# 09_-_M_2-SDMMC2.net
KiCad netlist of a schematic drawn in Altium Designer
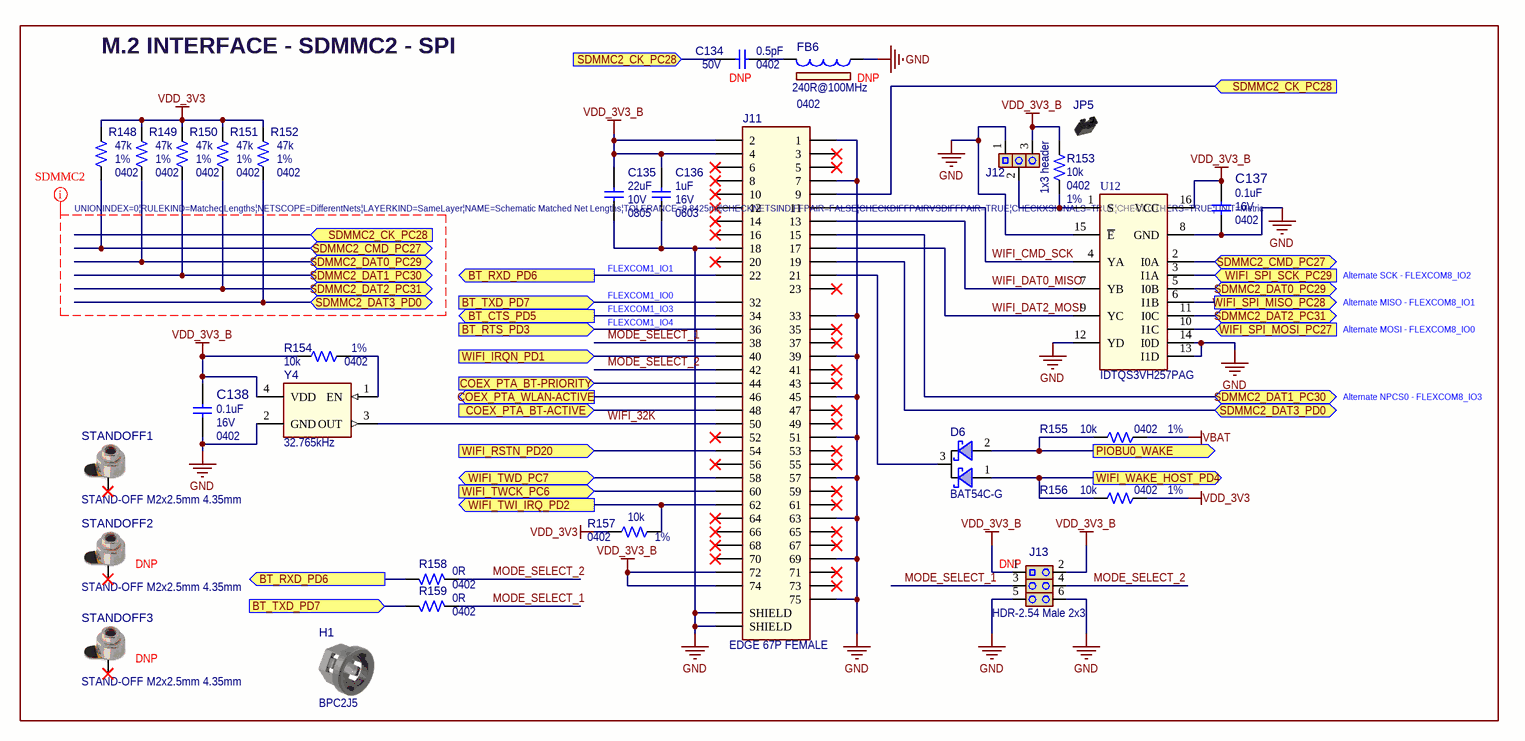
[diagram p0: 09 - M.2-SDMMC2.SchDoc]

(export (version "E")
  (design (tool "Eeschema 10.0.6"))
  (components
    (comp (ref "C134")
      (value "0.5pF")
      (footprint "CAP_C_0402")
      (fields
        (field (name "VOLTAGE") "50V")
        (field (name "PACKAGE") "0402")
        (field (name "TOLERANCE") "0.25pF")
        (field (name "POPULATED") "DNP")
        (field (name "Comment") "Capacitor NP")
      )
      (libsource (lib "MCHP-CDB") (part "Capacitor NP"))
    )
    (comp (ref "C135")
      (value "22uF")
      (footprint "CAP_C_0805")
      (fields
        (field (name "VOLTAGE") "10V")
        (field (name "PACKAGE") "0805")
        (field (name "TOLERANCE") "20%")
        (field (name "Comment") "Capacitor NP")
        (field (name "OWNER") "Razvan Cristescu")
      )
      (libsource (lib "MCHP-CDB") (part "Capacitor NP"))
    )
    (comp (ref "C136")
      (value "1uF")
      (footprint "CAP_C_0603")
      (fields
        (field (name "VOLTAGE") "16V")
        (field (name "PACKAGE") "0603")
        (field (name "TOLERANCE") "10%")
        (field (name "Comment") "Capacitor NP")
      )
      (libsource (lib "MCHP-CDB") (part "Capacitor NP"))
    )
    (comp (ref "C137")
      (value "0.1uF")
      (footprint "CAP_C_0402")
      (fields
        (field (name "VOLTAGE") "16V")
        (field (name "PACKAGE") "0402")
        (field (name "TOLERANCE") "10%")
        (field (name "Comment") "Capacitor NP")
        (field (name "OWNER") "Sompoch Loboonlert")
      )
      (libsource (lib "MCHP-CDB") (part "Capacitor NP"))
    )
    (comp (ref "C138")
      (value "0.1uF")
      (footprint "CAP_C_0402")
      (fields
        (field (name "VOLTAGE") "16V")
        (field (name "PACKAGE") "0402")
        (field (name "TOLERANCE") "10%")
        (field (name "Comment") "Capacitor NP")
        (field (name "OWNER") "Sompoch Loboonlert")
      )
      (libsource (lib "MCHP-CDB") (part "Capacitor NP"))
    )
    (comp (ref "D6")
      (value "BAT54C-G")
      (footprint "SOT-23-3")
      (fields
        (field (name "POWER") "225mW")
        (field (name "Comment") "Diode Schottky Dual CK")
        (field (name "OWNER") "Cristina Salanti")
      )
      (libsource (lib "MCHP-CDB") (part "Diode Schottky Dual CK"))
    )
    (comp (ref "FB6")
      (value "240R@100MHz")
      (footprint "IND_C_0402")
      (fields
        (field (name "PACKAGE") "0402")
        (field (name "POPULATED") "DNP")
        (field (name "Comment") "Ferrite Bead")
        (field (name "OWNER") "Joerg Buehrer")
      )
      (libsource (lib "MCHP-CDB") (part "Ferrite Bead"))
    )
    (comp (ref "H1")
      (value "BPC2J5")
      (footprint "BPC2J5")
      (fields (field (name "OWNER") "Dragos Danaila"))
      (libsource (lib "MCHP-CDB") (part "BPC2J5"))
    )
    (comp (ref "J11")
      (value "EDGE 67P FEMALE")
      (footprint "CON_EDGE-CARD_SMD_RA_TE_2199230-4")
      (fields
        (field (name "Comment") "CONN EDGE DUAL FEMALE_2199230-4")
        (field (name "OWNER") "Pilar Alcaine")
      )
      (libsource (lib "MCHP-CDB") (part "CONN EDGE DUAL FEMALE_2199230-4"))
    )
    (comp (ref "J12")
      (value "1x3 header")
      (footprint "HDR_M_2.54_1x3")
      (fields (field (name "Comment") "Header 1x3") (field (name "OWNER") "Dragos Danaila"))
      (libsource (lib "MCHP-CDB") (part "Header 1x3"))
    )
    (comp (ref "J13")
      (value "HDR-2.54 Male 2x3")
      (footprint "HDR_M_2.54_2x3")
      (fields (field (name "POPULATED") "DNP") (field (name "Comment") "Header 2x3"))
      (libsource (lib "MCHP-CDB") (part "Header 2x3"))
    )
    (comp (ref "JP5")
      (value "Jumper Mechanical")
      (footprint "Jumper_Mechanical")
      (fields (field (name "OWNER") "Narasimha Murthy"))
      (libsource (lib "MCHP-CDB") (part "Jumper Mechanical"))
    )
    (comp (ref "R148")
      (value "47k")
      (footprint "RES_C_0402")
      (description "Resistor")
      (fields
        (field (name "PACKAGE") "0402")
        (field (name "TOLERANCE") "1%")
        (field (name "VOLTAGE") "50V")
        (field (name "POWER") "1/10W")
        (field (name "OWNER") "Mike Ragsdale")
      )
      (libsource (lib "MCHP-CDB") (part "Resistor"))
    )
    (comp (ref "R149")
      (value "47k")
      (footprint "RES_C_0402")
      (description "Resistor")
      (fields
        (field (name "PACKAGE") "0402")
        (field (name "TOLERANCE") "1%")
        (field (name "VOLTAGE") "50V")
        (field (name "POWER") "1/10W")
        (field (name "OWNER") "Mike Ragsdale")
      )
      (libsource (lib "MCHP-CDB") (part "Resistor"))
    )
    (comp (ref "R150")
      (value "47k")
      (footprint "RES_C_0402")
      (description "Resistor")
      (fields
        (field (name "PACKAGE") "0402")
        (field (name "TOLERANCE") "1%")
        (field (name "VOLTAGE") "50V")
        (field (name "POWER") "1/10W")
        (field (name "OWNER") "Mike Ragsdale")
      )
      (libsource (lib "MCHP-CDB") (part "Resistor"))
    )
    (comp (ref "R151")
      (value "47k")
      (footprint "RES_C_0402")
      (description "Resistor")
      (fields
        (field (name "PACKAGE") "0402")
        (field (name "TOLERANCE") "1%")
        (field (name "VOLTAGE") "50V")
        (field (name "POWER") "1/10W")
        (field (name "OWNER") "Mike Ragsdale")
      )
      (libsource (lib "MCHP-CDB") (part "Resistor"))
    )
    (comp (ref "R152")
      (value "47k")
      (footprint "RES_C_0402")
      (description "Resistor")
      (fields
        (field (name "PACKAGE") "0402")
        (field (name "TOLERANCE") "1%")
        (field (name "VOLTAGE") "50V")
        (field (name "POWER") "1/10W")
        (field (name "OWNER") "Mike Ragsdale")
      )
      (libsource (lib "MCHP-CDB") (part "Resistor"))
    )
    (comp (ref "R153")
      (value "10k")
      (footprint "RES_C_0402")
      (description "Resistor")
      (fields
        (field (name "PACKAGE") "0402")
        (field (name "TOLERANCE") "1%")
        (field (name "VOLTAGE") "50V")
        (field (name "POWER") "1/10W")
        (field (name "OWNER") "Brent Lanphear")
      )
      (libsource (lib "MCHP-CDB") (part "Resistor"))
    )
    (comp (ref "R154")
      (value "10k")
      (footprint "RES_C_0402")
      (description "Resistor")
      (fields
        (field (name "PACKAGE") "0402")
        (field (name "TOLERANCE") "1%")
        (field (name "VOLTAGE") "50V")
        (field (name "POWER") "1/10W")
        (field (name "OWNER") "Brent Lanphear")
      )
      (libsource (lib "MCHP-CDB") (part "Resistor"))
    )
    (comp (ref "R155")
      (value "10k")
      (footprint "RES_C_0402")
      (description "Resistor")
      (fields
        (field (name "PACKAGE") "0402")
        (field (name "TOLERANCE") "1%")
        (field (name "VOLTAGE") "50V")
        (field (name "POWER") "1/10W")
        (field (name "OWNER") "Brent Lanphear")
      )
      (libsource (lib "MCHP-CDB") (part "Resistor"))
    )
    (comp (ref "R156")
      (value "10k")
      (footprint "RES_C_0402")
      (description "Resistor")
      (fields
        (field (name "PACKAGE") "0402")
        (field (name "TOLERANCE") "1%")
        (field (name "VOLTAGE") "50V")
        (field (name "POWER") "1/10W")
        (field (name "OWNER") "Brent Lanphear")
      )
      (libsource (lib "MCHP-CDB") (part "Resistor"))
    )
    (comp (ref "R157")
      (value "10k")
      (footprint "RES_C_0402")
      (description "Resistor")
      (fields
        (field (name "PACKAGE") "0402")
        (field (name "TOLERANCE") "1%")
        (field (name "VOLTAGE") "50V")
        (field (name "POWER") "1/10W")
        (field (name "OWNER") "Brent Lanphear")
      )
      (libsource (lib "MCHP-CDB") (part "Resistor"))
    )
    (comp (ref "R158")
      (value "0R")
      (footprint "RES_C_0402")
      (description "Resistor")
      (fields
        (field (name "PACKAGE") "0402")
        (field (name "POWER") "1/16W")
        (field (name "OWNER") "Sompoch Loboonlert")
      )
      (libsource (lib "") (part "Resistor_1"))
    )
    (comp (ref "R159")
      (value "0R")
      (footprint "RES_C_0402")
      (description "Resistor")
      (fields
        (field (name "PACKAGE") "0402")
        (field (name "POWER") "1/16W")
        (field (name "OWNER") "Sompoch Loboonlert")
      )
      (libsource (lib "") (part "Resistor_1"))
    )
    (comp (ref "STANDOFF1")
      (value "STAND-OFF M2x2.5mm 4.35mm")
      (footprint "MECH_HW_STAND-OFF_9774025243")
      (fields (field (name "Comment") "Standoff M-F") (field (name "OWNER") "Pilar Alcaine"))
      (libsource (lib "MCHP-CDB") (part "MECH_HW_STAND-OFF_TH_SOLDERABLE"))
    )
    (comp (ref "STANDOFF2")
      (value "STAND-OFF M2x2.5mm 4.35mm")
      (footprint "MECH_HW_STAND-OFF_9774025243")
      (fields
        (field (name "POPULATED") "DNP")
        (field (name "Comment") "Standoff M-F")
        (field (name "OWNER") "Pilar Alcaine")
      )
      (libsource (lib "MCHP-CDB") (part "MECH_HW_STAND-OFF_TH_SOLDERABLE"))
    )
    (comp (ref "STANDOFF3")
      (value "STAND-OFF M2x2.5mm 4.35mm")
      (footprint "MECH_HW_STAND-OFF_9774025243")
      (fields
        (field (name "POPULATED") "DNP")
        (field (name "Comment") "Standoff M-F")
        (field (name "OWNER") "Pilar Alcaine")
      )
      (libsource (lib "MCHP-CDB") (part "MECH_HW_STAND-OFF_TH_SOLDERABLE"))
    )
    (comp (ref "U12")
      (value "IDTQS3VH257PAG")
      (footprint "TSSOP-16")
      (fields (field (name "Comment") "IDTQS3VH257 TSSOP-16") (field (name "OWNER") "Ilie Galan"))
      (libsource (lib "MCHP-CDB") (part "IDTQS3VH257 TSSOP-16"))
    )
    (comp (ref "Y4")
      (value "32.765kHz")
      (footprint "OSCILLATOR_ASAK_L2W1.6H0.7")
      (fields
        (field (name "VOLTAGE") "3.3V")
        (field (name "TOLERANCE") "3ppm")
        (field (name "Comment") "OSCILLATOR 4 Pins")
        (field (name "OWNER") "Ilie Galan")
      )
      (libsource (lib "MCHP-CDB") (part "OSCILLATOR 4 Pins"))
    )
  )
  (nets
    (net (code "1") (name "/BT_CTS_PD5") (class "Default")
      (node (ref "J11") (pin "34") (pinfunction "34_34") (pintype "passive"))
    )
    (net (code "2") (name "/BT_RTS_PD3") (class "Default")
      (node (ref "J11") (pin "36") (pinfunction "36_36") (pintype "passive"))
    )
    (net (code "3") (name "/BT_RXD_PD6") (class "Default")
      (node (ref "J11") (pin "22") (pinfunction "22_22") (pintype "passive"))
      (node (ref "R158") (pin "1") (pinfunction "1_1") (pintype "passive"))
    )
    (net (code "4") (name "/BT_TXD_PD7") (class "Default")
      (node (ref "J11") (pin "32") (pinfunction "32_32") (pintype "passive"))
      (node (ref "R159") (pin "1") (pinfunction "1_1") (pintype "passive"))
    )
    (net (code "5") (name "/COEX_PTA_BT-ACTIVE") (class "Default")
      (node (ref "J11") (pin "48") (pinfunction "48_48") (pintype "passive"))
    )
    (net (code "6") (name "/COEX_PTA_BT-PRIORITY") (class "Default")
      (node (ref "J11") (pin "44") (pinfunction "44_44") (pintype "passive"))
    )
    (net (code "7") (name "/COEX_PTA_WLAN-ACTIVE") (class "Default")
      (node (ref "J11") (pin "46") (pinfunction "46_46") (pintype "passive"))
    )
    (net (code "8") (name "/MODE_SELECT_1") (class "Default")
      (node (ref "J11") (pin "38") (pinfunction "38_38") (pintype "passive"))
      (node (ref "J13") (pin "3") (pinfunction "3_3") (pintype "passive"))
      (node (ref "R159") (pin "2") (pinfunction "2_2") (pintype "passive"))
    )
    (net (code "9") (name "/MODE_SELECT_2") (class "Default")
      (node (ref "J11") (pin "42") (pinfunction "42_42") (pintype "passive"))
      (node (ref "J13") (pin "4") (pinfunction "4_4") (pintype "passive"))
      (node (ref "R158") (pin "2") (pinfunction "2_2") (pintype "passive"))
    )
    (net (code "10") (name "/PIOBU0_WAKE") (class "Default")
      (node (ref "D6") (pin "2") (pinfunction "A_2") (pintype "passive"))
      (node (ref "R155") (pin "2") (pinfunction "2_2") (pintype "passive"))
    )
    (net (code "11") (name "/SDMMC2_CK_PC28") (class "Default")
      (node (ref "C134") (pin "2") (pinfunction "2_2") (pintype "passive"))
      (node (ref "J11") (pin "9") (pinfunction "9_9") (pintype "passive"))
    )
    (net (code "12") (name "/SDMMC2_CMD_PC27") (class "Default")
      (node (ref "R148") (pin "2") (pinfunction "2_2") (pintype "passive"))
      (node (ref "U12") (pin "2") (pinfunction "I0A_2") (pintype "passive"))
    )
    (net (code "13") (name "/SDMMC2_DAT0_PC29") (class "Default")
      (node (ref "R149") (pin "2") (pinfunction "2_2") (pintype "passive"))
      (node (ref "U12") (pin "5") (pinfunction "I0B_5") (pintype "passive"))
    )
    (net (code "14") (name "/SDMMC2_DAT1_PC30") (class "Default")
      (node (ref "J11") (pin "15") (pinfunction "15_15") (pintype "passive"))
      (node (ref "R150") (pin "2") (pinfunction "2_2") (pintype "passive"))
    )
    (net (code "15") (name "/SDMMC2_DAT2_PC31") (class "Default")
      (node (ref "R151") (pin "2") (pinfunction "2_2") (pintype "passive"))
      (node (ref "U12") (pin "11") (pinfunction "I0C_11") (pintype "passive"))
    )
    (net (code "16") (name "/SDMMC2_DAT3_PD0") (class "Default")
      (node (ref "J11") (pin "19") (pinfunction "19_19") (pintype "passive"))
      (node (ref "R152") (pin "2") (pinfunction "2_2") (pintype "passive"))
    )
    (net (code "17") (name "/WIFI_32K") (class "Default")
      (node (ref "J11") (pin "50") (pinfunction "50_50") (pintype "passive"))
      (node (ref "Y4") (pin "3") (pinfunction "OUT_3") (pintype "output"))
    )
    (net (code "18") (name "/WIFI_CMD_SCK") (class "Default")
      (node (ref "J11") (pin "11") (pinfunction "11_11") (pintype "passive"))
      (node (ref "U12") (pin "4") (pinfunction "YA_4") (pintype "passive"))
    )
    (net (code "19") (name "/WIFI_DAT0_MISO") (class "Default")
      (node (ref "J11") (pin "13") (pinfunction "13_13") (pintype "passive"))
      (node (ref "U12") (pin "7") (pinfunction "YB_7") (pintype "passive"))
    )
    (net (code "20") (name "/WIFI_DAT2_MOSI") (class "Default")
      (node (ref "J11") (pin "17") (pinfunction "17_17") (pintype "passive"))
      (node (ref "U12") (pin "9") (pinfunction "YC_9") (pintype "passive"))
    )
    (net (code "21") (name "/WIFI_IRQN_PD1") (class "Default")
      (node (ref "J11") (pin "40") (pinfunction "40_40") (pintype "passive"))
    )
    (net (code "22") (name "/WIFI_RSTN_PD20") (class "Default")
      (node (ref "J11") (pin "54") (pinfunction "54_54") (pintype "passive"))
    )
    (net (code "23") (name "/WIFI_SPI_MISO_PC28") (class "Default")
      (node (ref "U12") (pin "6") (pinfunction "I1B_6") (pintype "passive"))
    )
    (net (code "24") (name "/WIFI_SPI_MOSI_PC27") (class "Default")
      (node (ref "U12") (pin "10") (pinfunction "I1C_10") (pintype "passive"))
    )
    (net (code "25") (name "/WIFI_SPI_SCK_PC29") (class "Default")
      (node (ref "U12") (pin "3") (pinfunction "I1A_3") (pintype "passive"))
    )
    (net (code "26") (name "/WIFI_TWCK_PC6") (class "Default")
      (node (ref "J11") (pin "60") (pinfunction "60_60") (pintype "passive"))
    )
    (net (code "27") (name "/WIFI_TWD_PC7") (class "Default")
      (node (ref "J11") (pin "58") (pinfunction "58_58") (pintype "passive"))
    )
    (net (code "28") (name "/WIFI_TWI_IRQ_PD2") (class "Default")
      (node (ref "J11") (pin "62") (pinfunction "62_62") (pintype "passive"))
      (node (ref "R157") (pin "1") (pinfunction "1_1") (pintype "passive"))
    )
    (net (code "29") (name "/WIFI_WAKE_HOST_PD4") (class "Default")
      (node (ref "D6") (pin "1") (pinfunction "A_1") (pintype "passive"))
      (node (ref "R156") (pin "2") (pinfunction "2_2") (pintype "passive"))
    )
    (net (code "30") (name "GND") (class "Default")
      (node (ref "C135") (pin "1") (pinfunction "1_1") (pintype "passive"))
      (node (ref "C136") (pin "1") (pinfunction "1_1") (pintype "passive"))
      (node (ref "C137") (pin "2") (pinfunction "2_2") (pintype "passive"))
      (node (ref "C138") (pin "2") (pinfunction "2_2") (pintype "passive"))
      (node (ref "FB6") (pin "1") (pinfunction "1_1") (pintype "passive"))
      (node (ref "J11") (pin "1") (pinfunction "1_1") (pintype "passive"))
      (node (ref "J11") (pin "18") (pinfunction "18_18") (pintype "passive"))
      (node (ref "J11") (pin "33") (pinfunction "33_33") (pintype "passive"))
      (node (ref "J11") (pin "39") (pinfunction "39_39") (pintype "passive"))
      (node (ref "J11") (pin "45") (pinfunction "45_45") (pintype "passive"))
      (node (ref "J11") (pin "51") (pinfunction "51_51") (pintype "passive"))
      (node (ref "J11") (pin "57") (pinfunction "57_57") (pintype "passive"))
      (node (ref "J11") (pin "63") (pinfunction "63_63") (pintype "passive"))
      (node (ref "J11") (pin "69") (pinfunction "69_69") (pintype "passive"))
      (node (ref "J11") (pin "7") (pinfunction "7_7") (pintype "passive"))
      (node (ref "J11") (pin "75") (pinfunction "75_75") (pintype "passive"))
      (node (ref "J11") (pin "S1") (pinfunction "SHIELD_S1") (pintype "passive"))
      (node (ref "J11") (pin "S2") (pinfunction "SHIELD_S2") (pintype "passive"))
      (node (ref "J12") (pin "1") (pinfunction "1_1") (pintype "passive"))
      (node (ref "J13") (pin "5") (pinfunction "5_5") (pintype "passive"))
      (node (ref "J13") (pin "6") (pinfunction "6_6") (pintype "passive"))
      (node (ref "U12") (pin "12") (pinfunction "YD_12") (pintype "passive"))
      (node (ref "U12") (pin "13") (pinfunction "I1D_13") (pintype "passive"))
      (node (ref "U12") (pin "14") (pinfunction "I0D_14") (pintype "passive"))
      (node (ref "U12") (pin "15") (pinfunction "~{E}_15") (pintype "passive"))
      (node (ref "U12") (pin "8") (pinfunction "GND_8") (pintype "passive"))
      (node (ref "Y4") (pin "2") (pinfunction "GND_2") (pintype "power_in"))
    )
    (net (code "31") (name "Net-(C134-Pad1)") (class "Default")
      (node (ref "C134") (pin "1") (pinfunction "1_1") (pintype "passive"))
      (node (ref "FB6") (pin "2") (pinfunction "2_2") (pintype "passive"))
    )
    (net (code "32") (name "Net-(D6-KK)") (class "Default")
      (node (ref "D6") (pin "3") (pinfunction "KK_3") (pintype "passive"))
      (node (ref "J11") (pin "21") (pinfunction "21_21") (pintype "passive"))
    )
    (net (code "33") (name "Net-(U12-S)") (class "Default")
      (node (ref "J12") (pin "2") (pinfunction "2_2") (pintype "passive"))
      (node (ref "R153") (pin "2") (pinfunction "2_2") (pintype "passive"))
      (node (ref "U12") (pin "1") (pinfunction "S_1") (pintype "passive"))
    )
    (net (code "34") (name "Net-(Y4-EN)") (class "Default")
      (node (ref "R154") (pin "1") (pinfunction "1_1") (pintype "passive"))
      (node (ref "Y4") (pin "1") (pinfunction "EN_1") (pintype "input"))
    )
    (net (code "35") (name "VBAT") (class "Default")
      (node (ref "R155") (pin "1") (pinfunction "1_1") (pintype "passive"))
    )
    (net (code "36") (name "VDD_3V3") (class "Default")
      (node (ref "R148") (pin "1") (pinfunction "1_1") (pintype "passive"))
      (node (ref "R149") (pin "1") (pinfunction "1_1") (pintype "passive"))
      (node (ref "R150") (pin "1") (pinfunction "1_1") (pintype "passive"))
      (node (ref "R151") (pin "1") (pinfunction "1_1") (pintype "passive"))
      (node (ref "R152") (pin "1") (pinfunction "1_1") (pintype "passive"))
      (node (ref "R156") (pin "1") (pinfunction "1_1") (pintype "passive"))
      (node (ref "R157") (pin "2") (pinfunction "2_2") (pintype "passive"))
    )
    (net (code "37") (name "VDD_3V3_B") (class "Default")
      (node (ref "C135") (pin "2") (pinfunction "2_2") (pintype "passive"))
      (node (ref "C136") (pin "2") (pinfunction "2_2") (pintype "passive"))
      (node (ref "C137") (pin "1") (pinfunction "1_1") (pintype "passive"))
      (node (ref "C138") (pin "1") (pinfunction "1_1") (pintype "passive"))
      (node (ref "J11") (pin "2") (pinfunction "2_2") (pintype "passive"))
      (node (ref "J11") (pin "4") (pinfunction "4_4") (pintype "passive"))
      (node (ref "J11") (pin "72") (pinfunction "72_72") (pintype "passive"))
      (node (ref "J11") (pin "74") (pinfunction "74_74") (pintype "passive"))
      (node (ref "J12") (pin "3") (pinfunction "3_3") (pintype "passive"))
      (node (ref "J13") (pin "1") (pinfunction "1_1") (pintype "passive"))
      (node (ref "J13") (pin "2") (pinfunction "2_2") (pintype "passive"))
      (node (ref "R153") (pin "1") (pinfunction "1_1") (pintype "passive"))
      (node (ref "R154") (pin "2") (pinfunction "2_2") (pintype "passive"))
      (node (ref "U12") (pin "16") (pinfunction "VCC_16") (pintype "passive"))
      (node (ref "Y4") (pin "4") (pinfunction "VDD_4") (pintype "power_in"))
    )
    (net (code "38") (name "unconnected-(J11-Pad3)") (class "Default")
      (node (ref "J11") (pin "3") (pinfunction "3_3") (pintype "passive+no_connect"))
    )
    (net (code "39") (name "unconnected-(J11-Pad5)") (class "Default")
      (node (ref "J11") (pin "5") (pinfunction "5_5") (pintype "passive+no_connect"))
    )
    (net (code "40") (name "unconnected-(J11-Pad6)") (class "Default")
      (node (ref "J11") (pin "6") (pinfunction "6_6") (pintype "passive+no_connect"))
    )
    (net (code "41") (name "unconnected-(J11-Pad8)") (class "Default")
      (node (ref "J11") (pin "8") (pinfunction "8_8") (pintype "passive+no_connect"))
    )
    (net (code "42") (name "unconnected-(J11-Pad10)") (class "Default")
      (node (ref "J11") (pin "10") (pinfunction "10_10") (pintype "passive+no_connect"))
    )
    (net (code "43") (name "unconnected-(J11-Pad12)") (class "Default")
      (node (ref "J11") (pin "12") (pinfunction "12_12") (pintype "passive+no_connect"))
    )
    (net (code "44") (name "unconnected-(J11-Pad14)") (class "Default")
      (node (ref "J11") (pin "14") (pinfunction "14_14") (pintype "passive+no_connect"))
    )
    (net (code "45") (name "unconnected-(J11-Pad16)") (class "Default")
      (node (ref "J11") (pin "16") (pinfunction "16_16") (pintype "passive+no_connect"))
    )
    (net (code "46") (name "unconnected-(J11-Pad20)") (class "Default")
      (node (ref "J11") (pin "20") (pinfunction "20_20") (pintype "passive+no_connect"))
    )
    (net (code "47") (name "unconnected-(J11-Pad23)") (class "Default")
      (node (ref "J11") (pin "23") (pinfunction "23_23") (pintype "passive+no_connect"))
    )
    (net (code "48") (name "unconnected-(J11-Pad35)") (class "Default")
      (node (ref "J11") (pin "35") (pinfunction "35_35") (pintype "passive+no_connect"))
    )
    (net (code "49") (name "unconnected-(J11-Pad37)") (class "Default")
      (node (ref "J11") (pin "37") (pinfunction "37_37") (pintype "passive+no_connect"))
    )
    (net (code "50") (name "unconnected-(J11-Pad41)") (class "Default")
      (node (ref "J11") (pin "41") (pinfunction "41_41") (pintype "passive+no_connect"))
    )
    (net (code "51") (name "unconnected-(J11-Pad43)") (class "Default")
      (node (ref "J11") (pin "43") (pinfunction "43_43") (pintype "passive+no_connect"))
    )
    (net (code "52") (name "unconnected-(J11-Pad47)") (class "Default")
      (node (ref "J11") (pin "47") (pinfunction "47_47") (pintype "passive+no_connect"))
    )
    (net (code "53") (name "unconnected-(J11-Pad49)") (class "Default")
      (node (ref "J11") (pin "49") (pinfunction "49_49") (pintype "passive+no_connect"))
    )
    (net (code "54") (name "unconnected-(J11-Pad52)") (class "Default")
      (node (ref "J11") (pin "52") (pinfunction "52_52") (pintype "passive+no_connect"))
    )
    (net (code "55") (name "unconnected-(J11-Pad53)") (class "Default")
      (node (ref "J11") (pin "53") (pinfunction "53_53") (pintype "passive+no_connect"))
    )
    (net (code "56") (name "unconnected-(J11-Pad55)") (class "Default")
      (node (ref "J11") (pin "55") (pinfunction "55_55") (pintype "passive+no_connect"))
    )
    (net (code "57") (name "unconnected-(J11-Pad56)") (class "Default")
      (node (ref "J11") (pin "56") (pinfunction "56_56") (pintype "passive+no_connect"))
    )
    (net (code "58") (name "unconnected-(J11-Pad59)") (class "Default")
      (node (ref "J11") (pin "59") (pinfunction "59_59") (pintype "passive+no_connect"))
    )
    (net (code "59") (name "unconnected-(J11-Pad61)") (class "Default")
      (node (ref "J11") (pin "61") (pinfunction "61_61") (pintype "passive+no_connect"))
    )
    (net (code "60") (name "unconnected-(J11-Pad64)") (class "Default")
      (node (ref "J11") (pin "64") (pinfunction "64_64") (pintype "passive+no_connect"))
    )
    (net (code "61") (name "unconnected-(J11-Pad65)") (class "Default")
      (node (ref "J11") (pin "65") (pinfunction "65_65") (pintype "passive+no_connect"))
    )
    (net (code "62") (name "unconnected-(J11-Pad66)") (class "Default")
      (node (ref "J11") (pin "66") (pinfunction "66_66") (pintype "passive+no_connect"))
    )
    (net (code "63") (name "unconnected-(J11-Pad67)") (class "Default")
      (node (ref "J11") (pin "67") (pinfunction "67_67") (pintype "passive+no_connect"))
    )
    (net (code "64") (name "unconnected-(J11-Pad68)") (class "Default")
      (node (ref "J11") (pin "68") (pinfunction "68_68") (pintype "passive+no_connect"))
    )
    (net (code "65") (name "unconnected-(J11-Pad70)") (class "Default")
      (node (ref "J11") (pin "70") (pinfunction "70_70") (pintype "passive+no_connect"))
    )
    (net (code "66") (name "unconnected-(J11-Pad71)") (class "Default")
      (node (ref "J11") (pin "71") (pinfunction "71_71") (pintype "passive+no_connect"))
    )
    (net (code "67") (name "unconnected-(J11-Pad73)") (class "Default")
      (node (ref "J11") (pin "73") (pinfunction "73_73") (pintype "passive+no_connect"))
    )
    (net (code "68") (name "unconnected-(STANDOFF1-Pad1)") (class "Default")
      (node (ref "STANDOFF1") (pin "1") (pinfunction "1_1") (pintype "power_in+no_connect"))
    )
    (net (code "69") (name "unconnected-(STANDOFF2-Pad1)") (class "Default")
      (node (ref "STANDOFF2") (pin "1") (pinfunction "1_1") (pintype "power_in+no_connect"))
    )
    (net (code "70") (name "unconnected-(STANDOFF3-Pad1)") (class "Default")
      (node (ref "STANDOFF3") (pin "1") (pinfunction "1_1") (pintype "power_in+no_connect"))
    )
  )
)
